# transmission_end_copy.net
KiCad netlist of a schematic drawn in EAGLE
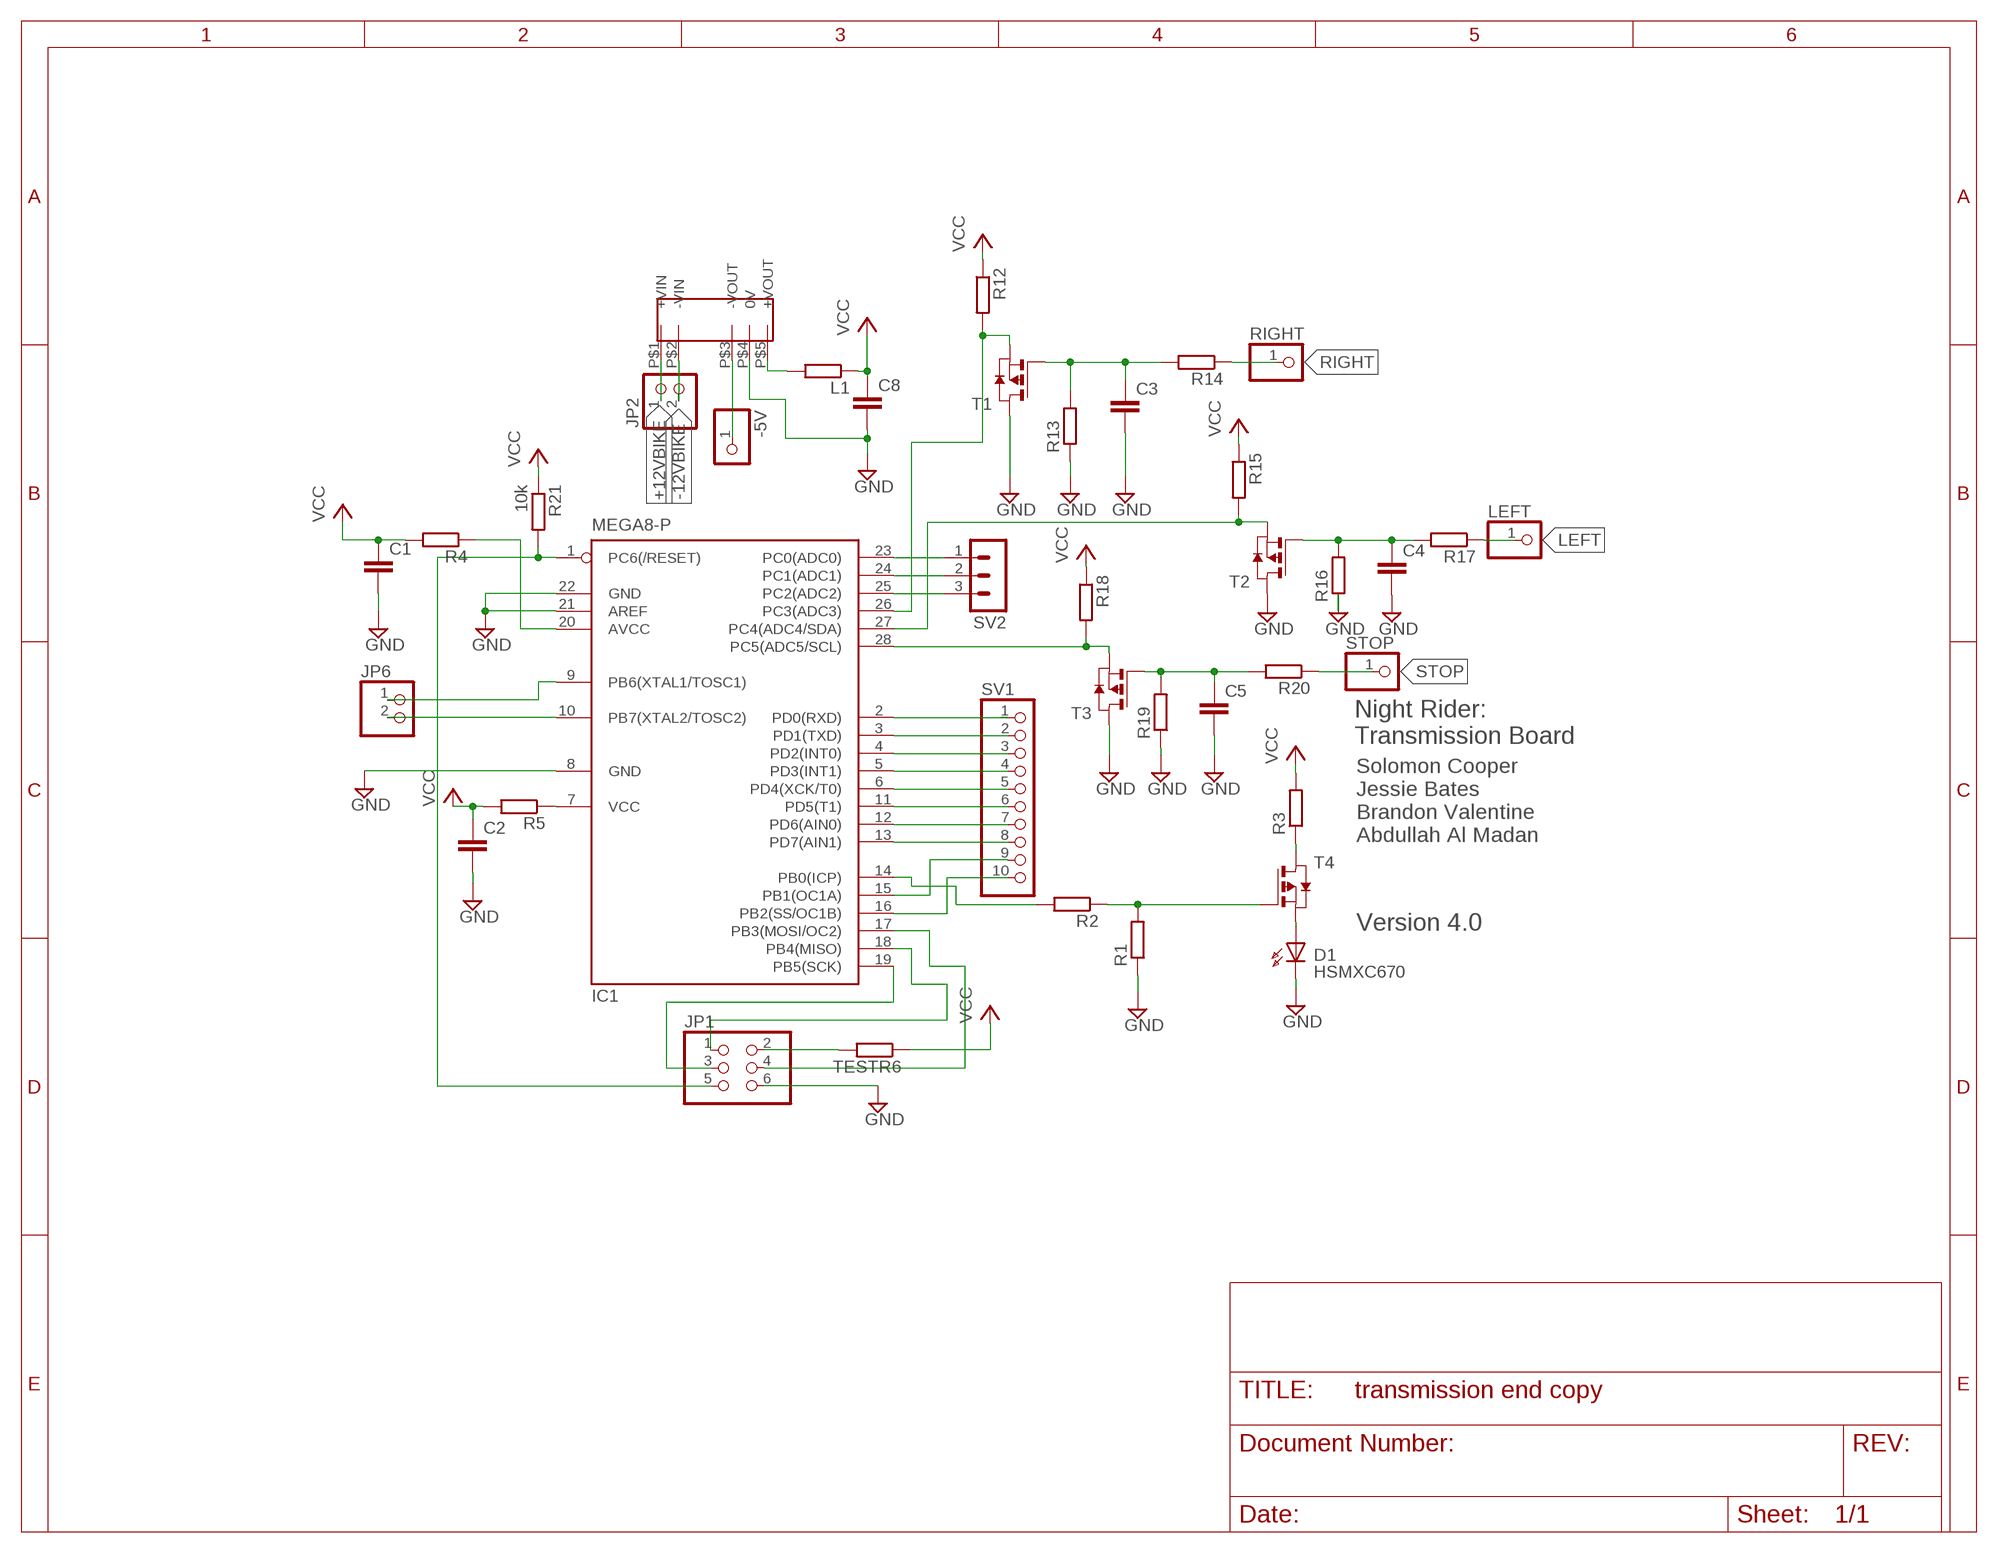
[diagram p0: schematic, sheet 1]

(export (version "E")
  (design (tool "Eeschema 10.0.6"))
  (components
    (comp (ref "-5V")
      (value "PINHD-1X1")
      (footprint "eagle-import:1X01")
      (libsource (lib "eagle-import") (part "PINHD-1X1"))
    )
    (comp (ref "C1")
      (value "C-EUC0805")
      (footprint "eagle-import:C0805")
      (libsource (lib "eagle-import") (part "C-EUC0805"))
    )
    (comp (ref "C2")
      (value "C-EUC0805")
      (footprint "eagle-import:C0805")
      (libsource (lib "eagle-import") (part "C-EUC0805"))
    )
    (comp (ref "C3")
      (value "C-EUC0805")
      (footprint "eagle-import:C0805")
      (libsource (lib "eagle-import") (part "C-EUC0805"))
    )
    (comp (ref "C4")
      (value "C-EUC0805")
      (footprint "eagle-import:C0805")
      (libsource (lib "eagle-import") (part "C-EUC0805"))
    )
    (comp (ref "C5")
      (value "C-EUC0805")
      (footprint "eagle-import:C0805")
      (libsource (lib "eagle-import") (part "C-EUC0805"))
    )
    (comp (ref "C8")
      (value "C-EUC0805")
      (footprint "eagle-import:C0805")
      (libsource (lib "eagle-import") (part "C-EUC0805"))
    )
    (comp (ref "D1")
      (value "HSMXC670")
      (footprint "eagle-import:HSMXC670")
      (fields (field (name "OC_FARNELL") "unknown") (field (name "OC_NEWARK") "unknown"))
      (libsource (lib "eagle-import") (part "HSMXC670"))
    )
    (comp (ref "IC1")
      (value "MEGA8-P")
      (footprint "eagle-import:DIL28-3")
      (libsource (lib "eagle-import") (part "MEGA8-P"))
    )
    (comp (ref "JP1")
      (value "PINHD-2X3")
      (footprint "eagle-import:2X03")
      (libsource (lib "eagle-import") (part "PINHD-2X3"))
    )
    (comp (ref "JP2")
      (value "PINHD-1X2")
      (footprint "eagle-import:1X02")
      (libsource (lib "eagle-import") (part "PINHD-1X2"))
    )
    (comp (ref "JP6")
      (value "PINHD-1X2")
      (footprint "eagle-import:1X02")
      (libsource (lib "eagle-import") (part "PINHD-1X2"))
    )
    (comp (ref "L1")
      (value "R-EU_M0805")
      (footprint "eagle-import:M0805")
      (libsource (lib "eagle-import") (part "R-EU_M0805"))
    )
    (comp (ref "LEFT")
      (value "PINHD-1X1")
      (footprint "eagle-import:1X01")
      (libsource (lib "eagle-import") (part "PINHD-1X1"))
    )
    (comp (ref "R1")
      (value "R-EU_M0805")
      (footprint "eagle-import:M0805")
      (libsource (lib "eagle-import") (part "R-EU_M0805"))
    )
    (comp (ref "R2")
      (value "R-EU_M0805")
      (footprint "eagle-import:M0805")
      (libsource (lib "eagle-import") (part "R-EU_M0805"))
    )
    (comp (ref "R3")
      (value "R-EU_M0805")
      (footprint "eagle-import:M0805")
      (libsource (lib "eagle-import") (part "R-EU_M0805"))
    )
    (comp (ref "R4")
      (value "R-EU_M0805")
      (footprint "eagle-import:M0805")
      (libsource (lib "eagle-import") (part "R-EU_M0805"))
    )
    (comp (ref "R5")
      (value "R-EU_M0805")
      (footprint "eagle-import:M0805")
      (libsource (lib "eagle-import") (part "R-EU_M0805"))
    )
    (comp (ref "R12")
      (value "R-EU_M0805")
      (footprint "eagle-import:M0805")
      (libsource (lib "eagle-import") (part "R-EU_M0805"))
    )
    (comp (ref "R13")
      (value "R-EU_M0805")
      (footprint "eagle-import:M0805")
      (libsource (lib "eagle-import") (part "R-EU_M0805"))
    )
    (comp (ref "R14")
      (value "R-EU_M0805")
      (footprint "eagle-import:M0805")
      (libsource (lib "eagle-import") (part "R-EU_M0805"))
    )
    (comp (ref "R15")
      (value "R-EU_M0805")
      (footprint "eagle-import:M0805")
      (libsource (lib "eagle-import") (part "R-EU_M0805"))
    )
    (comp (ref "R16")
      (value "R-EU_M0805")
      (footprint "eagle-import:M0805")
      (libsource (lib "eagle-import") (part "R-EU_M0805"))
    )
    (comp (ref "R17")
      (value "R-EU_M0805")
      (footprint "eagle-import:M0805")
      (libsource (lib "eagle-import") (part "R-EU_M0805"))
    )
    (comp (ref "R18")
      (value "R-EU_M0805")
      (footprint "eagle-import:M0805")
      (libsource (lib "eagle-import") (part "R-EU_M0805"))
    )
    (comp (ref "R19")
      (value "R-EU_M0805")
      (footprint "eagle-import:M0805")
      (libsource (lib "eagle-import") (part "R-EU_M0805"))
    )
    (comp (ref "R20")
      (value "R-EU_M0805")
      (footprint "eagle-import:M0805")
      (libsource (lib "eagle-import") (part "R-EU_M0805"))
    )
    (comp (ref "R21")
      (value "10k")
      (footprint "eagle-import:M0805")
      (libsource (lib "eagle-import") (part "R-EU_M0805"))
    )
    (comp (ref "RIGHT")
      (value "PINHD-1X1")
      (footprint "eagle-import:1X01")
      (libsource (lib "eagle-import") (part "PINHD-1X1"))
    )
    (comp (ref "STOP")
      (value "PINHD-1X1")
      (footprint "eagle-import:1X01")
      (libsource (lib "eagle-import") (part "PINHD-1X1"))
    )
    (comp (ref "SV1")
      (value "PINHD-1X10")
      (footprint "eagle-import:1X10")
      (libsource (lib "eagle-import") (part "PINHD-1X10"))
    )
    (comp (ref "SV2")
      (value "MA03-1")
      (footprint "eagle-import:MA03-1")
      (libsource (lib "eagle-import") (part "MA03-1"))
    )
    (comp (ref "T1")
      (value "PMOSSOT23")
      (footprint "eagle-import:SOT-23")
      (fields (field (name "OC_FARNELL") "unknown") (field (name "OC_NEWARK") "unknown"))
      (libsource (lib "eagle-import") (part "PMOSSOT23"))
    )
    (comp (ref "T2")
      (value "PMOSSOT23")
      (footprint "eagle-import:SOT-23")
      (libsource (lib "eagle-import") (part "PMOSSOT23"))
    )
    (comp (ref "T3")
      (value "PMOSSOT23")
      (footprint "eagle-import:SOT-23")
      (libsource (lib "eagle-import") (part "PMOSSOT23"))
    )
    (comp (ref "T4")
      (value "PMOSSOT23")
      (footprint "eagle-import:SOT-23")
      (fields (field (name "OC_FARNELL") "unknown") (field (name "OC_NEWARK") "unknown"))
      (libsource (lib "eagle-import") (part "PMOSSOT23"))
    )
    (comp (ref "TESTR6")
      (value "R-EU_M0805")
      (footprint "eagle-import:M0805")
      (libsource (lib "eagle-import") (part "R-EU_M0805"))
    )
    (comp (ref "U$1")
      (value "NKA1205SC")
      (footprint "eagle-import:NKA1205SC")
      (libsource (lib "eagle-import") (part "NKA1205SC"))
    )
  )
  (nets
    (net (code "1") (name "+12VBIKE") (class "Default")
      (node (ref "JP2") (pin "1") (pinfunction "1_1") (pintype "passive"))
      (node (ref "U$1") (pin "P$1") (pinfunction "+VIN_P$1") (pintype "bidirectional"))
    )
    (net (code "2") (name "-12VBIKE") (class "Default")
      (node (ref "JP2") (pin "2") (pinfunction "2_2") (pintype "passive"))
      (node (ref "U$1") (pin "P$2") (pinfunction "-VIN_P$2") (pintype "bidirectional"))
    )
    (net (code "3") (name "GND") (class "Default")
      (node (ref "C1") (pin "2") (pinfunction "2_2") (pintype "passive"))
      (node (ref "C2") (pin "2") (pinfunction "2_2") (pintype "passive"))
      (node (ref "C3") (pin "2") (pinfunction "2_2") (pintype "passive"))
      (node (ref "C4") (pin "2") (pinfunction "2_2") (pintype "passive"))
      (node (ref "C5") (pin "2") (pinfunction "2_2") (pintype "passive"))
      (node (ref "C8") (pin "2") (pinfunction "2_2") (pintype "passive"))
      (node (ref "D1") (pin "K") (pinfunction "C_K") (pintype "passive"))
      (node (ref "IC1") (pin "21") (pinfunction "AREF_21") (pintype "passive"))
      (node (ref "IC1") (pin "22") (pinfunction "GND_22") (pintype "power_in"))
      (node (ref "IC1") (pin "8") (pinfunction "GND_8") (pintype "power_in"))
      (node (ref "JP1") (pin "6") (pinfunction "6_6") (pintype "passive"))
      (node (ref "R1") (pin "1") (pinfunction "1_1") (pintype "passive"))
      (node (ref "R13") (pin "1") (pinfunction "1_1") (pintype "passive"))
      (node (ref "R16") (pin "1") (pinfunction "1_1") (pintype "passive"))
      (node (ref "R19") (pin "1") (pinfunction "1_1") (pintype "passive"))
      (node (ref "T1") (pin "1") (pinfunction "D_1") (pintype "passive"))
      (node (ref "T2") (pin "1") (pinfunction "D_1") (pintype "passive"))
      (node (ref "T3") (pin "1") (pinfunction "D_1") (pintype "passive"))
      (node (ref "U$1") (pin "P$4") (pinfunction "0V_P$4") (pintype "bidirectional"))
    )
    (net (code "4") (name "LEFT") (class "Default")
      (node (ref "LEFT") (pin "1") (pinfunction "1_1") (pintype "passive"))
      (node (ref "R17") (pin "1") (pinfunction "1_1") (pintype "passive"))
    )
    (net (code "5") (name "Net-(IC1-AVCC)") (class "Default")
      (node (ref "IC1") (pin "20") (pinfunction "AVCC_20") (pintype "power_in"))
      (node (ref "R4") (pin "1") (pinfunction "1_1") (pintype "passive"))
    )
    (net (code "6") (name "Net-(IC1-PB0(ICP))") (class "Default")
      (node (ref "IC1") (pin "14") (pinfunction "PB0(ICP)_14") (pintype "bidirectional"))
      (node (ref "R2") (pin "2") (pinfunction "2_2") (pintype "passive"))
    )
    (net (code "7") (name "Net-(IC1-PB1(OC1A))") (class "Default")
      (node (ref "IC1") (pin "15") (pinfunction "PB1(OC1A)_15") (pintype "bidirectional"))
      (node (ref "SV1") (pin "9") (pinfunction "9_9") (pintype "passive"))
    )
    (net (code "8") (name "Net-(IC1-PB2(SS{slash}OC1B))") (class "Default")
      (node (ref "IC1") (pin "16") (pinfunction "PB2(SS/OC1B)_16") (pintype "bidirectional"))
      (node (ref "SV1") (pin "10") (pinfunction "10_10") (pintype "passive"))
    )
    (net (code "9") (name "Net-(IC1-PB3(MOSI{slash}OC2))") (class "Default")
      (node (ref "IC1") (pin "17") (pinfunction "PB3(MOSI/OC2)_17") (pintype "bidirectional"))
      (node (ref "JP1") (pin "4") (pinfunction "4_4") (pintype "passive"))
    )
    (net (code "10") (name "Net-(IC1-PB4(MISO))") (class "Default")
      (node (ref "IC1") (pin "18") (pinfunction "PB4(MISO)_18") (pintype "bidirectional"))
      (node (ref "JP1") (pin "1") (pinfunction "1_1") (pintype "passive"))
    )
    (net (code "11") (name "Net-(IC1-PB5(SCK))") (class "Default")
      (node (ref "IC1") (pin "19") (pinfunction "PB5(SCK)_19") (pintype "bidirectional"))
      (node (ref "JP1") (pin "3") (pinfunction "3_3") (pintype "passive"))
    )
    (net (code "12") (name "Net-(IC1-PB6(XTAL1{slash}TOSC1))") (class "Default")
      (node (ref "IC1") (pin "9") (pinfunction "PB6(XTAL1/TOSC1)_9") (pintype "bidirectional"))
      (node (ref "JP6") (pin "1") (pinfunction "1_1") (pintype "passive"))
    )
    (net (code "13") (name "Net-(IC1-PB7(XTAL2{slash}TOSC2))") (class "Default")
      (node (ref "IC1") (pin "10") (pinfunction "PB7(XTAL2/TOSC2)_10") (pintype "bidirectional"))
      (node (ref "JP6") (pin "2") (pinfunction "2_2") (pintype "passive"))
    )
    (net (code "14") (name "Net-(IC1-PC0(ADC0))") (class "Default")
      (node (ref "IC1") (pin "23") (pinfunction "PC0(ADC0)_23") (pintype "bidirectional"))
      (node (ref "SV2") (pin "1") (pinfunction "1_1") (pintype "passive"))
    )
    (net (code "15") (name "Net-(IC1-PC1(ADC1))") (class "Default")
      (node (ref "IC1") (pin "24") (pinfunction "PC1(ADC1)_24") (pintype "bidirectional"))
      (node (ref "SV2") (pin "2") (pinfunction "2_2") (pintype "passive"))
    )
    (net (code "16") (name "Net-(IC1-PC2(ADC2))") (class "Default")
      (node (ref "IC1") (pin "25") (pinfunction "PC2(ADC2)_25") (pintype "bidirectional"))
      (node (ref "SV2") (pin "3") (pinfunction "3_3") (pintype "passive"))
    )
    (net (code "17") (name "Net-(IC1-PC3(ADC3))") (class "Default")
      (node (ref "IC1") (pin "26") (pinfunction "PC3(ADC3)_26") (pintype "bidirectional"))
      (node (ref "R12") (pin "2") (pinfunction "2_2") (pintype "passive"))
      (node (ref "T1") (pin "2") (pinfunction "S_2") (pintype "passive"))
    )
    (net (code "18") (name "Net-(IC1-PC4(ADC4{slash}SDA))") (class "Default")
      (node (ref "IC1") (pin "27") (pinfunction "PC4(ADC4/SDA)_27") (pintype "bidirectional"))
      (node (ref "R15") (pin "2") (pinfunction "2_2") (pintype "passive"))
      (node (ref "T2") (pin "2") (pinfunction "S_2") (pintype "passive"))
    )
    (net (code "19") (name "Net-(IC1-PC5(ADC5{slash}SCL))") (class "Default")
      (node (ref "IC1") (pin "28") (pinfunction "PC5(ADC5/SCL)_28") (pintype "bidirectional"))
      (node (ref "R18") (pin "2") (pinfunction "2_2") (pintype "passive"))
      (node (ref "T3") (pin "2") (pinfunction "S_2") (pintype "passive"))
    )
    (net (code "20") (name "Net-(IC1-PC6({slash}RESET))") (class "Default")
      (node (ref "IC1") (pin "1") (pinfunction "PC6(/RESET)_1") (pintype "bidirectional"))
      (node (ref "JP1") (pin "5") (pinfunction "5_5") (pintype "passive"))
      (node (ref "R21") (pin "2") (pinfunction "2_2") (pintype "passive"))
    )
    (net (code "21") (name "Net-(IC1-PD0(RXD))") (class "Default")
      (node (ref "IC1") (pin "2") (pinfunction "PD0(RXD)_2") (pintype "bidirectional"))
      (node (ref "SV1") (pin "1") (pinfunction "1_1") (pintype "passive"))
    )
    (net (code "22") (name "Net-(IC1-PD1(TXD))") (class "Default")
      (node (ref "IC1") (pin "3") (pinfunction "PD1(TXD)_3") (pintype "bidirectional"))
      (node (ref "SV1") (pin "2") (pinfunction "2_2") (pintype "passive"))
    )
    (net (code "23") (name "Net-(IC1-PD2(INT0))") (class "Default")
      (node (ref "IC1") (pin "4") (pinfunction "PD2(INT0)_4") (pintype "bidirectional"))
      (node (ref "SV1") (pin "3") (pinfunction "3_3") (pintype "passive"))
    )
    (net (code "24") (name "Net-(IC1-PD3(INT1))") (class "Default")
      (node (ref "IC1") (pin "5") (pinfunction "PD3(INT1)_5") (pintype "bidirectional"))
      (node (ref "SV1") (pin "4") (pinfunction "4_4") (pintype "passive"))
    )
    (net (code "25") (name "Net-(IC1-PD4(XCK{slash}T0))") (class "Default")
      (node (ref "IC1") (pin "6") (pinfunction "PD4(XCK/T0)_6") (pintype "bidirectional"))
      (node (ref "SV1") (pin "5") (pinfunction "5_5") (pintype "passive"))
    )
    (net (code "26") (name "Net-(IC1-PD5(T1))") (class "Default")
      (node (ref "IC1") (pin "11") (pinfunction "PD5(T1)_11") (pintype "bidirectional"))
      (node (ref "SV1") (pin "6") (pinfunction "6_6") (pintype "passive"))
    )
    (net (code "27") (name "Net-(IC1-PD6(AIN0))") (class "Default")
      (node (ref "IC1") (pin "12") (pinfunction "PD6(AIN0)_12") (pintype "bidirectional"))
      (node (ref "SV1") (pin "7") (pinfunction "7_7") (pintype "passive"))
    )
    (net (code "28") (name "Net-(IC1-PD7(AIN1))") (class "Default")
      (node (ref "IC1") (pin "13") (pinfunction "PD7(AIN1)_13") (pintype "bidirectional"))
      (node (ref "SV1") (pin "8") (pinfunction "8_8") (pintype "passive"))
    )
    (net (code "29") (name "Net-(IC1-VCC)") (class "Default")
      (node (ref "IC1") (pin "7") (pinfunction "VCC_7") (pintype "power_in"))
      (node (ref "R5") (pin "1") (pinfunction "1_1") (pintype "passive"))
    )
    (net (code "30") (name "Net-(JP1-Pad2)") (class "Default")
      (node (ref "JP1") (pin "2") (pinfunction "2_2") (pintype "passive"))
      (node (ref "TESTR6") (pin "2") (pinfunction "2_2") (pintype "passive"))
    )
    (net (code "31") (name "Net-(T1-G)") (class "Default")
      (node (ref "C3") (pin "1") (pinfunction "1_1") (pintype "passive"))
      (node (ref "R13") (pin "2") (pinfunction "2_2") (pintype "passive"))
      (node (ref "R14") (pin "2") (pinfunction "2_2") (pintype "passive"))
      (node (ref "T1") (pin "3") (pinfunction "G_3") (pintype "passive"))
    )
    (net (code "32") (name "Net-(T2-G)") (class "Default")
      (node (ref "C4") (pin "1") (pinfunction "1_1") (pintype "passive"))
      (node (ref "R16") (pin "2") (pinfunction "2_2") (pintype "passive"))
      (node (ref "R17") (pin "2") (pinfunction "2_2") (pintype "passive"))
      (node (ref "T2") (pin "3") (pinfunction "G_3") (pintype "passive"))
    )
    (net (code "33") (name "Net-(T3-G)") (class "Default")
      (node (ref "C5") (pin "1") (pinfunction "1_1") (pintype "passive"))
      (node (ref "R19") (pin "2") (pinfunction "2_2") (pintype "passive"))
      (node (ref "R20") (pin "2") (pinfunction "2_2") (pintype "passive"))
      (node (ref "T3") (pin "3") (pinfunction "G_3") (pintype "passive"))
    )
    (net (code "34") (name "Net-(T4-D)") (class "Default")
      (node (ref "R3") (pin "1") (pinfunction "1_1") (pintype "passive"))
      (node (ref "T4") (pin "1") (pinfunction "D_1") (pintype "passive"))
    )
    (net (code "35") (name "Net-(T4-G)") (class "Default")
      (node (ref "R1") (pin "2") (pinfunction "2_2") (pintype "passive"))
      (node (ref "R2") (pin "1") (pinfunction "1_1") (pintype "passive"))
      (node (ref "T4") (pin "3") (pinfunction "G_3") (pintype "passive"))
    )
    (net (code "36") (name "Net-(T4-S)") (class "Default")
      (node (ref "D1") (pin "A") (pinfunction "A_A") (pintype "passive"))
      (node (ref "T4") (pin "2") (pinfunction "S_2") (pintype "passive"))
    )
    (net (code "37") (name "Net-(U$1-+VOUT)") (class "Default")
      (node (ref "L1") (pin "2") (pinfunction "2_2") (pintype "passive"))
      (node (ref "U$1") (pin "P$5") (pinfunction "+VOUT_P$5") (pintype "bidirectional"))
    )
    (net (code "38") (name "Net-(U$1--VOUT)") (class "Default")
      (node (ref "-5V") (pin "1") (pinfunction "1_1") (pintype "passive"))
      (node (ref "U$1") (pin "P$3") (pinfunction "-VOUT_P$3") (pintype "bidirectional"))
    )
    (net (code "39") (name "RIGHT") (class "Default")
      (node (ref "R14") (pin "1") (pinfunction "1_1") (pintype "passive"))
      (node (ref "RIGHT") (pin "1") (pinfunction "1_1") (pintype "passive"))
    )
    (net (code "40") (name "STOP") (class "Default")
      (node (ref "R20") (pin "1") (pinfunction "1_1") (pintype "passive"))
      (node (ref "STOP") (pin "1") (pinfunction "1_1") (pintype "passive"))
    )
    (net (code "41") (name "VCC") (class "Default")
      (node (ref "C1") (pin "1") (pinfunction "1_1") (pintype "passive"))
      (node (ref "C2") (pin "1") (pinfunction "1_1") (pintype "passive"))
      (node (ref "C8") (pin "1") (pinfunction "1_1") (pintype "passive"))
      (node (ref "L1") (pin "1") (pinfunction "1_1") (pintype "passive"))
      (node (ref "R12") (pin "1") (pinfunction "1_1") (pintype "passive"))
      (node (ref "R15") (pin "1") (pinfunction "1_1") (pintype "passive"))
      (node (ref "R18") (pin "1") (pinfunction "1_1") (pintype "passive"))
      (node (ref "R21") (pin "1") (pinfunction "1_1") (pintype "passive"))
      (node (ref "R3") (pin "2") (pinfunction "2_2") (pintype "passive"))
      (node (ref "R4") (pin "2") (pinfunction "2_2") (pintype "passive"))
      (node (ref "R5") (pin "2") (pinfunction "2_2") (pintype "passive"))
      (node (ref "TESTR6") (pin "1") (pinfunction "1_1") (pintype "passive"))
    )
  )
)
